# SmartMatrixSD_V3.net
KiCad netlist of a schematic drawn in EAGLE
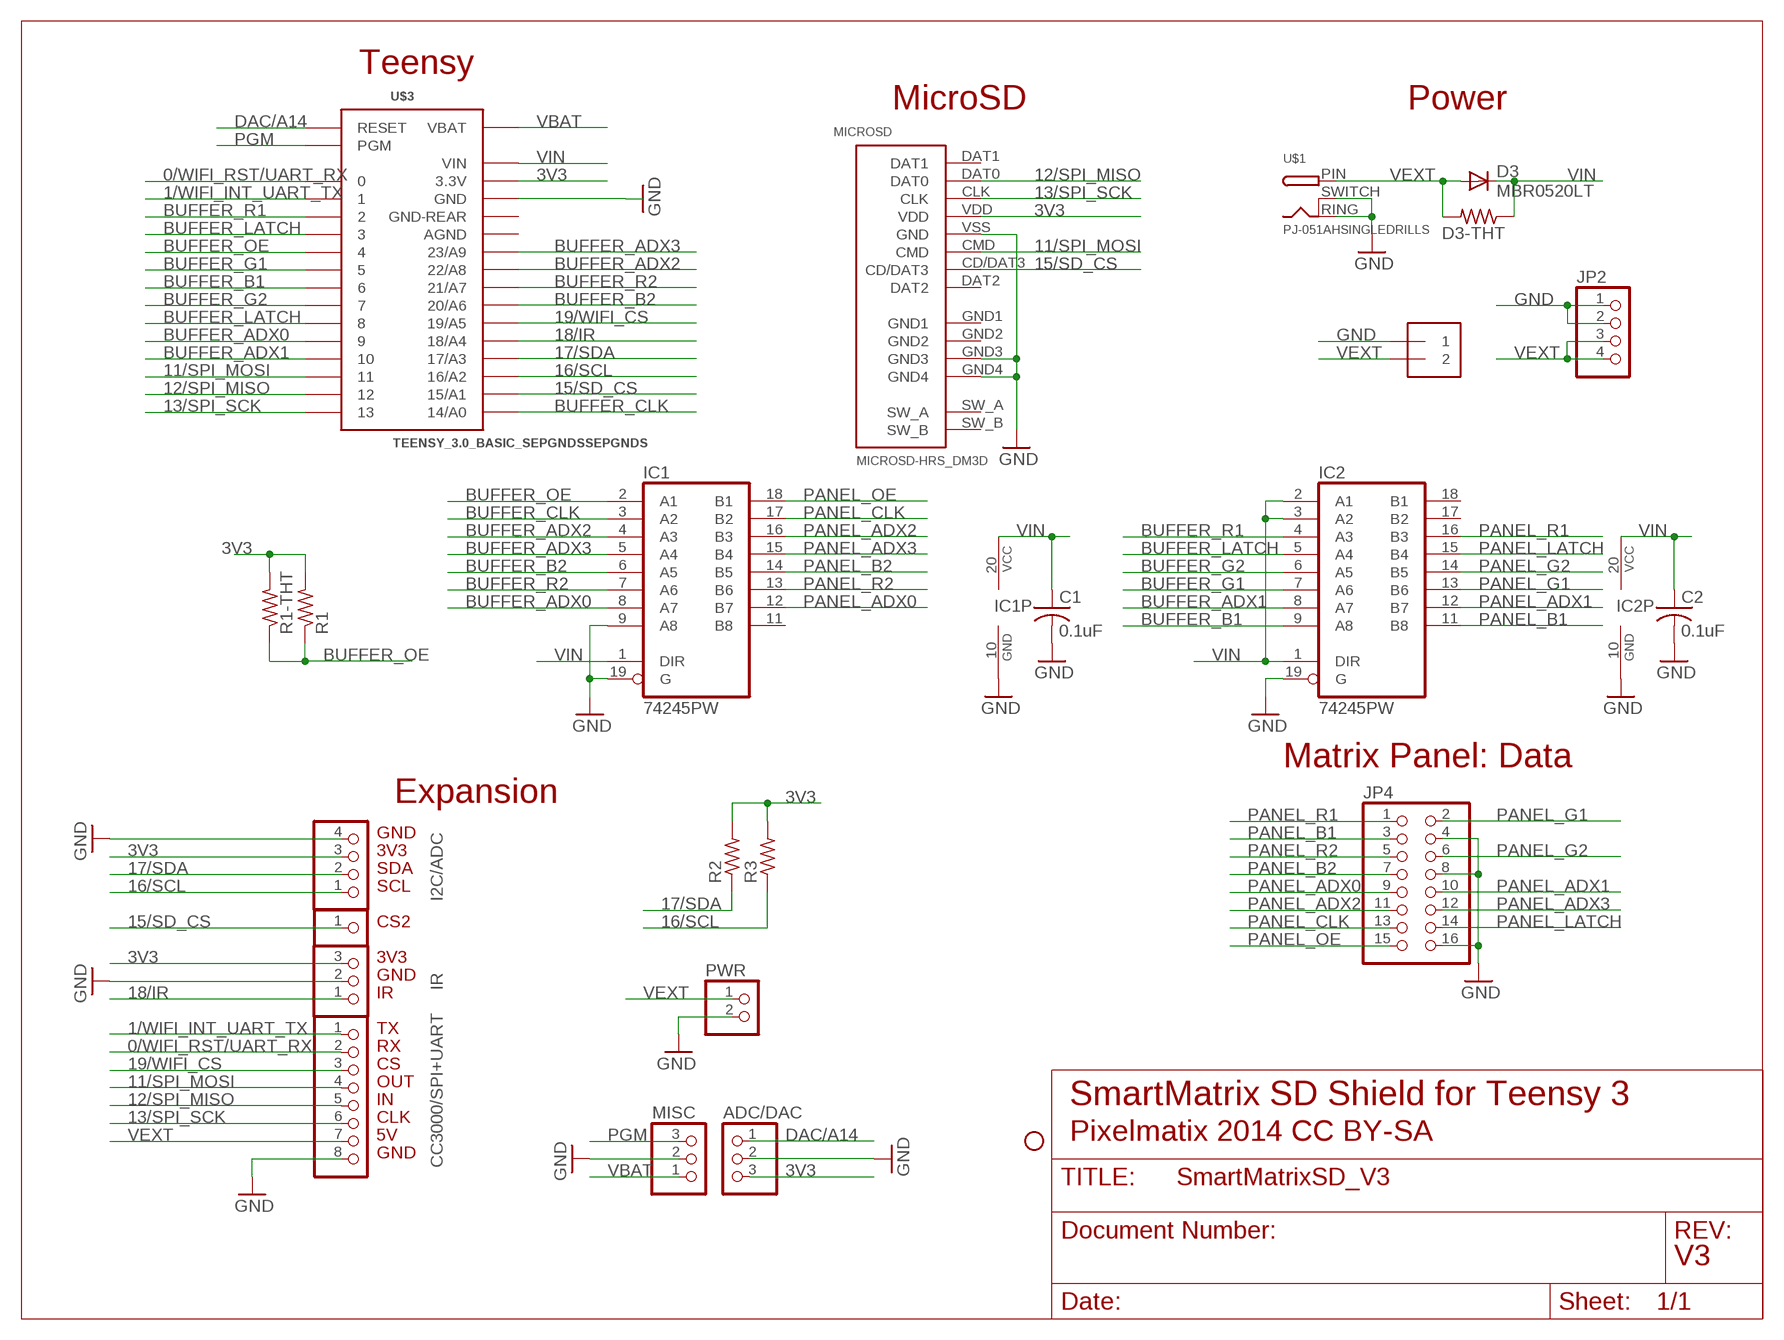
[diagram p0: schematic, sheet 1]

(export (version "E")
  (design (tool "Eeschema 10.0.6"))
  (components
    (comp (ref "ADC/DAC")
      (value "PINHD-1X03_2.54-S")
      (footprint "eagle-import:1X03-S")
      (libsource (lib "eagle-import") (part "PINHD-1X03_2.54-S"))
    )
    (comp (ref "C1")
      (value "0.1uF")
      (footprint "eagle-import:C0603")
      (fields (field (name "PARTNO") "CAP CER 0.1UF 10V 10% X7R 0805"))
      (libsource (lib "eagle-import") (part "C-USC0603"))
    )
    (comp (ref "C2")
      (value "0.1uF")
      (footprint "eagle-import:C0603")
      (fields (field (name "PARTNO") "CAP CER 0.1UF 10V 10% X7R 0805"))
      (libsource (lib "eagle-import") (part "C-USC0603"))
    )
    (comp (ref "CC3000/SPI+UART")
      (value "PINHD-1X08_2.54-S")
      (footprint "eagle-import:1X08-S")
      (libsource (lib "eagle-import") (part "PINHD-1X08_2.54-S"))
    )
    (comp (ref "CS2")
      (value "PINHD-1X01_2.54-S")
      (footprint "eagle-import:1X01-S")
      (libsource (lib "eagle-import") (part "PINHD-1X01_2.54-S"))
    )
    (comp (ref "D3")
      (value "MBR0520LT")
      (footprint "eagle-import:SOD123")
      (libsource (lib "eagle-import") (part "MBR0520LT"))
    )
    (comp (ref "D3-THT")
      (value "R-US_0207/2V")
      (footprint "eagle-import:0207_2V")
      (libsource (lib "eagle-import") (part "R-US_0207/2V"))
    )
    (comp (ref "I2C/ADC")
      (value "PINHD-1X04_2.54-S")
      (footprint "eagle-import:1X04-S")
      (libsource (lib "eagle-import") (part "pinhead-2_PINHD-1X04_2.54-S"))
    )
    (comp (ref "IC1")
      (value "74245PW")
      (footprint "eagle-import:TSSOP-20")
      (libsource (lib "eagle-import") (part "74245PW"))
    )
    (comp (ref "IC2")
      (value "74245PW")
      (footprint "eagle-import:TSSOP-20")
      (libsource (lib "eagle-import") (part "74245PW"))
    )
    (comp (ref "IR")
      (value "PINHD-1X03_2.54-S")
      (footprint "eagle-import:1X03-S")
      (libsource (lib "eagle-import") (part "PINHD-1X03_2.54-S"))
    )
    (comp (ref "J4")
      (value "1X2-5.0")
      (footprint "eagle-import:1X2-5.0MM")
      (libsource (lib "eagle-import") (part "1X2-5.0"))
    )
    (comp (ref "JP2")
      (value "PINHD-1X04_1.56")
      (footprint "eagle-import:1X04-1.56_")
      (libsource (lib "eagle-import") (part "PINHD-1X04_1.56"))
    )
    (comp (ref "JP4")
      (value "PINHD-2X08_2.54")
      (footprint "eagle-import:2X08")
      (libsource (lib "eagle-import") (part "PINHD-2X08_2.54"))
    )
    (comp (ref "JP5")
      (value "STAND-OFFSTAND-OFF-3MM")
      (footprint "eagle-import:STAND-OFF-3MM")
      (libsource (lib "eagle-import") (part "STAND-OFFSTAND-OFF-3MM"))
    )
    (comp (ref "MICROSD")
      (value "MICROSD-HRS_DM3D")
      (footprint "eagle-import:DM3D")
      (libsource (lib "eagle-import") (part "MICROSD-HRS_DM3D"))
    )
    (comp (ref "MISC")
      (value "PINHD-1X03_2.54-S")
      (footprint "eagle-import:1X03-S")
      (libsource (lib "eagle-import") (part "PINHD-1X03_2.54-S"))
    )
    (comp (ref "PWR")
      (value "PINHD-1X02_2.54-S")
      (footprint "eagle-import:1X02-S")
      (libsource (lib "eagle-import") (part "PINHD-1X02_2.54-S"))
    )
    (comp (ref "R1")
      (value "R-US_R0603")
      (footprint "eagle-import:R0603")
      (libsource (lib "eagle-import") (part "R-US_R0603"))
    )
    (comp (ref "R1-THT")
      (value "R-US_0207/2V")
      (footprint "eagle-import:0207_2V")
      (libsource (lib "eagle-import") (part "R-US_0207/2V"))
    )
    (comp (ref "R2")
      (value "R-US_0207/7")
      (footprint "eagle-import:0207_7")
      (libsource (lib "eagle-import") (part "R-US_0207/7"))
    )
    (comp (ref "R3")
      (value "R-US_0207/7")
      (footprint "eagle-import:0207_7")
      (libsource (lib "eagle-import") (part "R-US_0207/7"))
    )
    (comp (ref "U$1")
      (value "PJ-051AHSINGLEDRILLS")
      (footprint "eagle-import:PJ-051AH-SINGLEDRILLS")
      (libsource (lib "eagle-import") (part "PJ-051AHSINGLEDRILLS"))
    )
    (comp (ref "U$3")
      (value "TEENSY_3.0_BASIC_SEPGNDSSEPGNDS")
      (footprint "eagle-import:TEENSY_3.0_BASIC")
      (libsource (lib "eagle-import") (part "TEENSY_3.0_BASIC_SEPGNDSSEPGNDS"))
    )
  )
  (nets
    (net (code "1") (name "/0{slash}WIFI_RST{slash}UART_RX") (class "Default")
      (node (ref "CC3000/SPI+UART") (pin "2") (pinfunction "2_2") (pintype "passive"))
      (node (ref "U$3") (pin "0") (pinfunction "0_0") (pintype "bidirectional"))
    )
    (net (code "2") (name "/1{slash}WIFI_INT_UART_TX") (class "Default")
      (node (ref "CC3000/SPI+UART") (pin "1") (pinfunction "1_1") (pintype "passive"))
      (node (ref "U$3") (pin "1") (pinfunction "1_1") (pintype "bidirectional"))
    )
    (net (code "3") (name "/3V3") (class "Default")
      (node (ref "ADC/DAC") (pin "3") (pinfunction "3_3") (pintype "passive"))
      (node (ref "I2C/ADC") (pin "3") (pinfunction "3_3") (pintype "passive"))
      (node (ref "IR") (pin "3") (pinfunction "3_3") (pintype "passive"))
      (node (ref "MICROSD") (pin "VDD") (pinfunction "VDD_VDD") (pintype "bidirectional"))
      (node (ref "R1") (pin "2") (pinfunction "2_2") (pintype "passive"))
      (node (ref "R1-THT") (pin "2") (pinfunction "2_2") (pintype "passive"))
      (node (ref "R2") (pin "2") (pinfunction "2_2") (pintype "passive"))
      (node (ref "R3") (pin "2") (pinfunction "2_2") (pintype "passive"))
      (node (ref "U$3") (pin "3.3V") (pinfunction "3.3V_3.3V") (pintype "power_in"))
      (node (ref "U$3") (pin "3.3V1") (pinfunction "3.3V_3.3V1") (pintype "power_in"))
    )
    (net (code "4") (name "/11{slash}SPI_MOSI") (class "Default")
      (node (ref "CC3000/SPI+UART") (pin "4") (pinfunction "4_4") (pintype "passive"))
      (node (ref "MICROSD") (pin "CMD") (pinfunction "CMD_CMD") (pintype "bidirectional"))
      (node (ref "U$3") (pin "11") (pinfunction "11_11") (pintype "bidirectional"))
    )
    (net (code "5") (name "/12{slash}SPI_MISO") (class "Default")
      (node (ref "CC3000/SPI+UART") (pin "5") (pinfunction "5_5") (pintype "passive"))
      (node (ref "MICROSD") (pin "DAT0") (pinfunction "DAT0_DAT0") (pintype "bidirectional"))
      (node (ref "U$3") (pin "12") (pinfunction "12_12") (pintype "bidirectional"))
    )
    (net (code "6") (name "/13{slash}SPI_SCK") (class "Default")
      (node (ref "CC3000/SPI+UART") (pin "6") (pinfunction "6_6") (pintype "passive"))
      (node (ref "MICROSD") (pin "CLK") (pinfunction "CLK_CLK") (pintype "bidirectional"))
      (node (ref "U$3") (pin "13") (pinfunction "13_13") (pintype "bidirectional"))
    )
    (net (code "7") (name "/15{slash}SD_CS") (class "Default")
      (node (ref "CS2") (pin "1") (pinfunction "1_1") (pintype "passive"))
      (node (ref "MICROSD") (pin "CD/DAT3") (pinfunction "CD/DAT3_CD/DAT3") (pintype "bidirectional"))
      (node (ref "U$3") (pin "15/A1") (pinfunction "15/A1_15/A1") (pintype "bidirectional"))
    )
    (net (code "8") (name "/16{slash}SCL") (class "Default")
      (node (ref "I2C/ADC") (pin "1") (pinfunction "1_1") (pintype "passive"))
      (node (ref "R3") (pin "1") (pinfunction "1_1") (pintype "passive"))
      (node (ref "U$3") (pin "16/A2") (pinfunction "16/A2_16/A2") (pintype "bidirectional"))
    )
    (net (code "9") (name "/17{slash}SDA") (class "Default")
      (node (ref "I2C/ADC") (pin "2") (pinfunction "2_2") (pintype "passive"))
      (node (ref "R2") (pin "1") (pinfunction "1_1") (pintype "passive"))
      (node (ref "U$3") (pin "17/A3") (pinfunction "17/A3_17/A3") (pintype "bidirectional"))
    )
    (net (code "10") (name "/18{slash}IR") (class "Default")
      (node (ref "IR") (pin "1") (pinfunction "1_1") (pintype "passive"))
      (node (ref "U$3") (pin "18/A4") (pinfunction "18/A4_18/A4") (pintype "bidirectional"))
    )
    (net (code "11") (name "/19{slash}WIFI_CS") (class "Default")
      (node (ref "CC3000/SPI+UART") (pin "3") (pinfunction "3_3") (pintype "passive"))
      (node (ref "U$3") (pin "19/A5") (pinfunction "19/A5_19/A5") (pintype "bidirectional"))
    )
    (net (code "12") (name "/AGND") (class "Default")
      (node (ref "U$3") (pin "AGND") (pinfunction "AGND_AGND") (pintype "power_in"))
    )
    (net (code "13") (name "/BUFFER_ADX0") (class "Default")
      (node (ref "IC1") (pin "8") (pinfunction "A7_8") (pintype "bidirectional"))
      (node (ref "U$3") (pin "9") (pinfunction "9_9") (pintype "bidirectional"))
    )
    (net (code "14") (name "/BUFFER_ADX1") (class "Default")
      (node (ref "IC2") (pin "8") (pinfunction "A7_8") (pintype "bidirectional"))
      (node (ref "U$3") (pin "10") (pinfunction "10_10") (pintype "bidirectional"))
    )
    (net (code "15") (name "/BUFFER_ADX2") (class "Default")
      (node (ref "IC1") (pin "4") (pinfunction "A3_4") (pintype "bidirectional"))
      (node (ref "U$3") (pin "22/A8") (pinfunction "22/A8_22/A8") (pintype "bidirectional"))
    )
    (net (code "16") (name "/BUFFER_ADX3") (class "Default")
      (node (ref "IC1") (pin "5") (pinfunction "A4_5") (pintype "bidirectional"))
      (node (ref "U$3") (pin "23/A9") (pinfunction "23/A9_23/A9") (pintype "bidirectional"))
    )
    (net (code "17") (name "/BUFFER_B1") (class "Default")
      (node (ref "IC2") (pin "9") (pinfunction "A8_9") (pintype "bidirectional"))
      (node (ref "U$3") (pin "6") (pinfunction "6_6") (pintype "bidirectional"))
    )
    (net (code "18") (name "/BUFFER_B2") (class "Default")
      (node (ref "IC1") (pin "6") (pinfunction "A5_6") (pintype "bidirectional"))
      (node (ref "U$3") (pin "20/A6") (pinfunction "20/A6_20/A6") (pintype "bidirectional"))
    )
    (net (code "19") (name "/BUFFER_CLK") (class "Default")
      (node (ref "IC1") (pin "3") (pinfunction "A2_3") (pintype "bidirectional"))
      (node (ref "U$3") (pin "14/A0") (pinfunction "14/A0_14/A0") (pintype "bidirectional"))
    )
    (net (code "20") (name "/BUFFER_G1") (class "Default")
      (node (ref "IC2") (pin "7") (pinfunction "A6_7") (pintype "bidirectional"))
      (node (ref "U$3") (pin "5") (pinfunction "5_5") (pintype "bidirectional"))
    )
    (net (code "21") (name "/BUFFER_G2") (class "Default")
      (node (ref "IC2") (pin "6") (pinfunction "A5_6") (pintype "bidirectional"))
      (node (ref "U$3") (pin "7") (pinfunction "7_7") (pintype "bidirectional"))
    )
    (net (code "22") (name "/BUFFER_LATCH") (class "Default")
      (node (ref "IC2") (pin "5") (pinfunction "A4_5") (pintype "bidirectional"))
      (node (ref "U$3") (pin "3") (pinfunction "3_3") (pintype "bidirectional"))
      (node (ref "U$3") (pin "8") (pinfunction "8_8") (pintype "bidirectional"))
    )
    (net (code "23") (name "/BUFFER_OE") (class "Default")
      (node (ref "IC1") (pin "2") (pinfunction "A1_2") (pintype "bidirectional"))
      (node (ref "R1") (pin "1") (pinfunction "1_1") (pintype "passive"))
      (node (ref "R1-THT") (pin "1") (pinfunction "1_1") (pintype "passive"))
      (node (ref "U$3") (pin "4") (pinfunction "4_4") (pintype "bidirectional"))
    )
    (net (code "24") (name "/BUFFER_R1") (class "Default")
      (node (ref "IC2") (pin "4") (pinfunction "A3_4") (pintype "bidirectional"))
      (node (ref "U$3") (pin "2") (pinfunction "2_2") (pintype "bidirectional"))
    )
    (net (code "25") (name "/BUFFER_R2") (class "Default")
      (node (ref "IC1") (pin "7") (pinfunction "A6_7") (pintype "bidirectional"))
      (node (ref "U$3") (pin "21/A7") (pinfunction "21/A7_21/A7") (pintype "bidirectional"))
    )
    (net (code "26") (name "/DAC{slash}A14") (class "Default")
      (node (ref "ADC/DAC") (pin "1") (pinfunction "1_1") (pintype "passive"))
      (node (ref "U$3") (pin "RESET") (pinfunction "RESET_RESET") (pintype "bidirectional"))
    )
    (net (code "27") (name "/GND-REAR") (class "Default")
      (node (ref "U$3") (pin "GND1") (pinfunction "GND-REAR_GND1") (pintype "power_in"))
    )
    (net (code "28") (name "/PANEL_ADX0") (class "Default")
      (node (ref "IC1") (pin "12") (pinfunction "B7_12") (pintype "bidirectional"))
      (node (ref "JP4") (pin "9") (pinfunction "9_9") (pintype "passive"))
    )
    (net (code "29") (name "/PANEL_ADX1") (class "Default")
      (node (ref "IC2") (pin "12") (pinfunction "B7_12") (pintype "bidirectional"))
      (node (ref "JP4") (pin "10") (pinfunction "10_10") (pintype "passive"))
    )
    (net (code "30") (name "/PANEL_ADX2") (class "Default")
      (node (ref "IC1") (pin "16") (pinfunction "B3_16") (pintype "bidirectional"))
      (node (ref "JP4") (pin "11") (pinfunction "11_11") (pintype "passive"))
    )
    (net (code "31") (name "/PANEL_ADX3") (class "Default")
      (node (ref "IC1") (pin "15") (pinfunction "B4_15") (pintype "bidirectional"))
      (node (ref "JP4") (pin "12") (pinfunction "12_12") (pintype "passive"))
    )
    (net (code "32") (name "/PANEL_B1") (class "Default")
      (node (ref "IC2") (pin "11") (pinfunction "B8_11") (pintype "bidirectional"))
      (node (ref "JP4") (pin "3") (pinfunction "3_3") (pintype "passive"))
    )
    (net (code "33") (name "/PANEL_B2") (class "Default")
      (node (ref "IC1") (pin "14") (pinfunction "B5_14") (pintype "bidirectional"))
      (node (ref "JP4") (pin "7") (pinfunction "7_7") (pintype "passive"))
    )
    (net (code "34") (name "/PANEL_CLK") (class "Default")
      (node (ref "IC1") (pin "17") (pinfunction "B2_17") (pintype "bidirectional"))
      (node (ref "JP4") (pin "13") (pinfunction "13_13") (pintype "passive"))
    )
    (net (code "35") (name "/PANEL_G1") (class "Default")
      (node (ref "IC2") (pin "13") (pinfunction "B6_13") (pintype "bidirectional"))
      (node (ref "JP4") (pin "2") (pinfunction "2_2") (pintype "passive"))
    )
    (net (code "36") (name "/PANEL_G2") (class "Default")
      (node (ref "IC2") (pin "14") (pinfunction "B5_14") (pintype "bidirectional"))
      (node (ref "JP4") (pin "6") (pinfunction "6_6") (pintype "passive"))
    )
    (net (code "37") (name "/PANEL_LATCH") (class "Default")
      (node (ref "IC2") (pin "15") (pinfunction "B4_15") (pintype "bidirectional"))
      (node (ref "JP4") (pin "14") (pinfunction "14_14") (pintype "passive"))
    )
    (net (code "38") (name "/PANEL_OE") (class "Default")
      (node (ref "IC1") (pin "18") (pinfunction "B1_18") (pintype "bidirectional"))
      (node (ref "JP4") (pin "15") (pinfunction "15_15") (pintype "passive"))
    )
    (net (code "39") (name "/PANEL_R1") (class "Default")
      (node (ref "IC2") (pin "16") (pinfunction "B3_16") (pintype "bidirectional"))
      (node (ref "JP4") (pin "1") (pinfunction "1_1") (pintype "passive"))
    )
    (net (code "40") (name "/PANEL_R2") (class "Default")
      (node (ref "IC1") (pin "13") (pinfunction "B6_13") (pintype "bidirectional"))
      (node (ref "JP4") (pin "5") (pinfunction "5_5") (pintype "passive"))
    )
    (net (code "41") (name "/PGM") (class "Default")
      (node (ref "MISC") (pin "3") (pinfunction "3_3") (pintype "passive"))
      (node (ref "U$3") (pin "PGM") (pinfunction "PGM_PGM") (pintype "bidirectional"))
    )
    (net (code "42") (name "/VBAT") (class "Default")
      (node (ref "MISC") (pin "1") (pinfunction "1_1") (pintype "passive"))
      (node (ref "U$3") (pin "VBAT") (pinfunction "VBAT_VBAT") (pintype "power_in"))
    )
    (net (code "43") (name "/VEXT") (class "Default")
      (node (ref "CC3000/SPI+UART") (pin "7") (pinfunction "7_7") (pintype "passive"))
      (node (ref "D3") (pin "A") (pinfunction "A_A") (pintype "passive"))
      (node (ref "D3-THT") (pin "2") (pinfunction "2_2") (pintype "passive"))
      (node (ref "J4") (pin "2") (pinfunction "2_2") (pintype "passive"))
      (node (ref "JP2") (pin "3") (pinfunction "3_3") (pintype "passive"))
      (node (ref "JP2") (pin "4") (pinfunction "4_4") (pintype "passive"))
      (node (ref "PWR") (pin "1") (pinfunction "1_1") (pintype "passive"))
      (node (ref "U$1") (pin "PIN") (pinfunction "PWR_PIN") (pintype "power_in"))
    )
    (net (code "44") (name "/VIN") (class "Default")
      (node (ref "C1") (pin "1") (pinfunction "1_1") (pintype "passive"))
      (node (ref "C2") (pin "1") (pinfunction "1_1") (pintype "passive"))
      (node (ref "D3") (pin "C") (pinfunction "C_C") (pintype "passive"))
      (node (ref "D3-THT") (pin "1") (pinfunction "1_1") (pintype "passive"))
      (node (ref "IC1") (pin "1") (pinfunction "DIR_1") (pintype "input"))
      (node (ref "IC1") (pin "20") (pinfunction "VCC_20") (pintype "power_in"))
      (node (ref "IC2") (pin "1") (pinfunction "DIR_1") (pintype "input"))
      (node (ref "IC2") (pin "2") (pinfunction "A1_2") (pintype "bidirectional"))
      (node (ref "IC2") (pin "20") (pinfunction "VCC_20") (pintype "power_in"))
      (node (ref "IC2") (pin "3") (pinfunction "A2_3") (pintype "bidirectional"))
      (node (ref "U$3") (pin "VIN") (pinfunction "VIN_VIN") (pintype "power_in"))
    )
    (net (code "45") (name "GND") (class "Default")
      (node (ref "ADC/DAC") (pin "2") (pinfunction "2_2") (pintype "passive"))
      (node (ref "C1") (pin "2") (pinfunction "2_2") (pintype "passive"))
      (node (ref "C2") (pin "2") (pinfunction "2_2") (pintype "passive"))
      (node (ref "CC3000/SPI+UART") (pin "8") (pinfunction "8_8") (pintype "passive"))
      (node (ref "I2C/ADC") (pin "4") (pinfunction "4_4") (pintype "passive"))
      (node (ref "IC1") (pin "10") (pinfunction "GND_10") (pintype "power_in"))
      (node (ref "IC1") (pin "19") (pinfunction "G_19") (pintype "input"))
      (node (ref "IC1") (pin "9") (pinfunction "A8_9") (pintype "bidirectional"))
      (node (ref "IC2") (pin "10") (pinfunction "GND_10") (pintype "power_in"))
      (node (ref "IC2") (pin "19") (pinfunction "G_19") (pintype "input"))
      (node (ref "IR") (pin "2") (pinfunction "2_2") (pintype "passive"))
      (node (ref "J4") (pin "1") (pinfunction "1_1") (pintype "passive"))
      (node (ref "JP2") (pin "1") (pinfunction "1_1") (pintype "passive"))
      (node (ref "JP2") (pin "2") (pinfunction "2_2") (pintype "passive"))
      (node (ref "JP4") (pin "16") (pinfunction "16_16") (pintype "passive"))
      (node (ref "JP4") (pin "4") (pinfunction "4_4") (pintype "passive"))
      (node (ref "JP4") (pin "8") (pinfunction "8_8") (pintype "passive"))
      (node (ref "MICROSD") (pin "GND3") (pinfunction "GND3_GND3") (pintype "bidirectional"))
      (node (ref "MICROSD") (pin "GND4") (pinfunction "GND4_GND4") (pintype "bidirectional"))
      (node (ref "MICROSD") (pin "VSS") (pinfunction "GND_VSS") (pintype "bidirectional"))
      (node (ref "MISC") (pin "2") (pinfunction "2_2") (pintype "passive"))
      (node (ref "PWR") (pin "2") (pinfunction "2_2") (pintype "passive"))
      (node (ref "U$1") (pin "RING") (pinfunction "GND_RING") (pintype "power_in"))
      (node (ref "U$1") (pin "SWITCH") (pinfunction "GNDBREAK_SWITCH") (pintype "power_in"))
      (node (ref "U$3") (pin "GND") (pinfunction "GND_GND") (pintype "power_in"))
    )
    (net (code "46") (name "unconnected-(IC1A-B8-Pad11)") (class "Default")
      (node (ref "IC1") (pin "11") (pinfunction "B8_11") (pintype "bidirectional"))
    )
    (net (code "47") (name "unconnected-(IC2A-B1-Pad18)") (class "Default")
      (node (ref "IC2") (pin "18") (pinfunction "B1_18") (pintype "bidirectional"))
    )
    (net (code "48") (name "unconnected-(IC2A-B2-Pad17)") (class "Default")
      (node (ref "IC2") (pin "17") (pinfunction "B2_17") (pintype "bidirectional"))
    )
    (net (code "49") (name "unconnected-(MICROSD-PadDAT1)") (class "Default")
      (node (ref "MICROSD") (pin "DAT1") (pinfunction "DAT1_DAT1") (pintype "bidirectional"))
    )
    (net (code "50") (name "unconnected-(MICROSD-PadDAT2)") (class "Default")
      (node (ref "MICROSD") (pin "DAT2") (pinfunction "DAT2_DAT2") (pintype "bidirectional"))
    )
    (net (code "51") (name "unconnected-(MICROSD-PadGND1)") (class "Default")
      (node (ref "MICROSD") (pin "GND1") (pinfunction "GND1_GND1") (pintype "bidirectional"))
    )
    (net (code "52") (name "unconnected-(MICROSD-PadGND2)") (class "Default")
      (node (ref "MICROSD") (pin "GND2") (pinfunction "GND2_GND2") (pintype "bidirectional"))
    )
    (net (code "53") (name "unconnected-(MICROSD-PadSW_A)") (class "Default")
      (node (ref "MICROSD") (pin "SW_A") (pinfunction "SW_A_SW_A") (pintype "bidirectional"))
    )
    (net (code "54") (name "unconnected-(MICROSD-PadSW_B)") (class "Default")
      (node (ref "MICROSD") (pin "SW_B") (pinfunction "SW_B_SW_B") (pintype "bidirectional"))
    )
  )
)
